# USB.net
KiCad netlist of a schematic drawn in Altium Designer
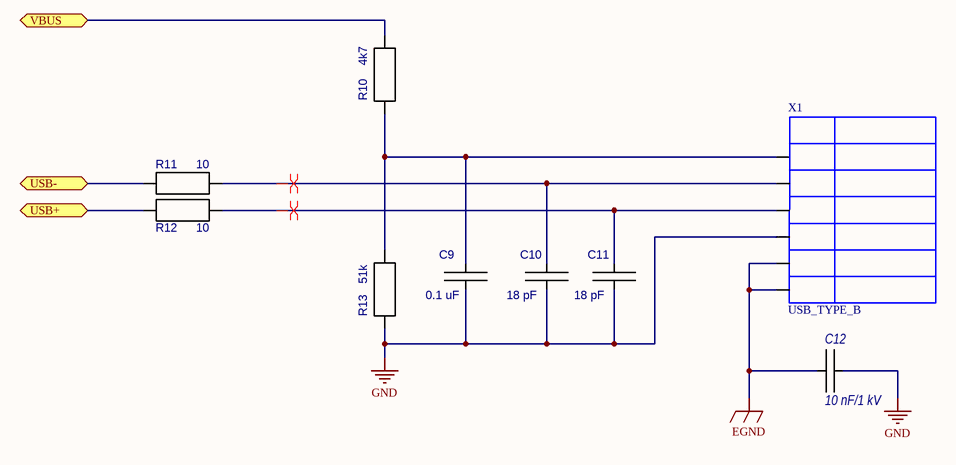
[diagram p0: USB.SchDoc]

(export (version "E")
  (design (tool "Eeschema 10.0.6"))
  (components
    (comp (ref "C9")
      (value "0.1 uF")
      (footprint "CAP_0805")
      (description "CAP_0805")
      (libsource (lib "PA_control_board") (part "CAP_0805"))
    )
    (comp (ref "C10")
      (value "18 pF")
      (footprint "CAP_0805")
      (description "CAP_0805")
      (libsource (lib "PA_control_board") (part "CAP_0805"))
    )
    (comp (ref "C11")
      (value "18 pF")
      (footprint "CAP_0805")
      (description "CAP_0805")
      (libsource (lib "PA_control_board") (part "CAP_0805"))
    )
    (comp (ref "C12") (value "10 nF/1 kV") (libsource (lib "PA_control_board") (part "Cap")))
    (comp (ref "R10")
      (value "4k7")
      (footprint "RES_0805")
      (description "RES_0805")
      (libsource (lib "PA_control_board") (part "RES_0805"))
    )
    (comp (ref "R11")
      (value "10")
      (footprint "RES_0805")
      (description "RES_0805")
      (libsource (lib "PA_control_board") (part "RES_0805"))
    )
    (comp (ref "R12")
      (value "10")
      (footprint "RES_0805")
      (description "RES_0805")
      (libsource (lib "PA_control_board") (part "RES_0805"))
    )
    (comp (ref "R13")
      (value "51k")
      (footprint "RES_0805")
      (description "RES_0805")
      (libsource (lib "PA_control_board") (part "RES_0805"))
    )
    (comp (ref "X1")
      (value "USB_TYPE_B")
      (footprint "USB_TypeB_Tyco")
      (libsource (lib "PA_control_board") (part "USB_TYPE_B"))
    )
  )
  (nets
    (net (code "1") (name "/USB+") (class "Default")
      (node (ref "R12") (pin "2") (pinfunction "2_2") (pintype "passive"))
    )
    (net (code "2") (name "/USB-") (class "Default")
      (node (ref "R11") (pin "2") (pinfunction "2_2") (pintype "passive"))
    )
    (net (code "3") (name "/VBUS") (class "Default")
      (node (ref "R10") (pin "1") (pinfunction "1_1") (pintype "passive"))
    )
    (net (code "4") (name "EGND") (class "Default")
      (node (ref "C12") (pin "1") (pinfunction "1_1") (pintype "passive"))
      (node (ref "X1") (pin "5") (pintype "passive"))
      (node (ref "X1") (pin "6") (pintype "passive"))
    )
    (net (code "5") (name "GND") (class "Default")
      (node (ref "C10") (pin "2") (pinfunction "2_2") (pintype "passive"))
      (node (ref "C11") (pin "2") (pinfunction "2_2") (pintype "passive"))
      (node (ref "C12") (pin "2") (pinfunction "2_2") (pintype "passive"))
      (node (ref "C9") (pin "2") (pinfunction "2_2") (pintype "passive"))
      (node (ref "R13") (pin "2") (pinfunction "2_2") (pintype "passive"))
      (node (ref "X1") (pin "4") (pintype "passive"))
    )
    (net (code "6") (name "Net-(C9-Pad1)") (class "Default")
      (node (ref "C9") (pin "1") (pinfunction "1_1") (pintype "passive"))
      (node (ref "R10") (pin "2") (pinfunction "2_2") (pintype "passive"))
      (node (ref "R13") (pin "1") (pinfunction "1_1") (pintype "passive"))
      (node (ref "X1") (pin "1") (pintype "passive"))
    )
    (net (code "7") (name "Net-(C10-Pad1)") (class "Default")
      (node (ref "C10") (pin "1") (pinfunction "1_1") (pintype "passive"))
      (node (ref "R11") (pin "1") (pinfunction "1_1") (pintype "passive"))
      (node (ref "X1") (pin "2") (pintype "passive"))
    )
    (net (code "8") (name "Net-(C11-Pad1)") (class "Default")
      (node (ref "C11") (pin "1") (pinfunction "1_1") (pintype "passive"))
      (node (ref "R12") (pin "1") (pinfunction "1_1") (pintype "passive"))
      (node (ref "X1") (pin "3") (pintype "passive"))
    )
  )
)
